# RobotCtrl_Base_Power.net
KiCad netlist of a schematic drawn in Altium Designer
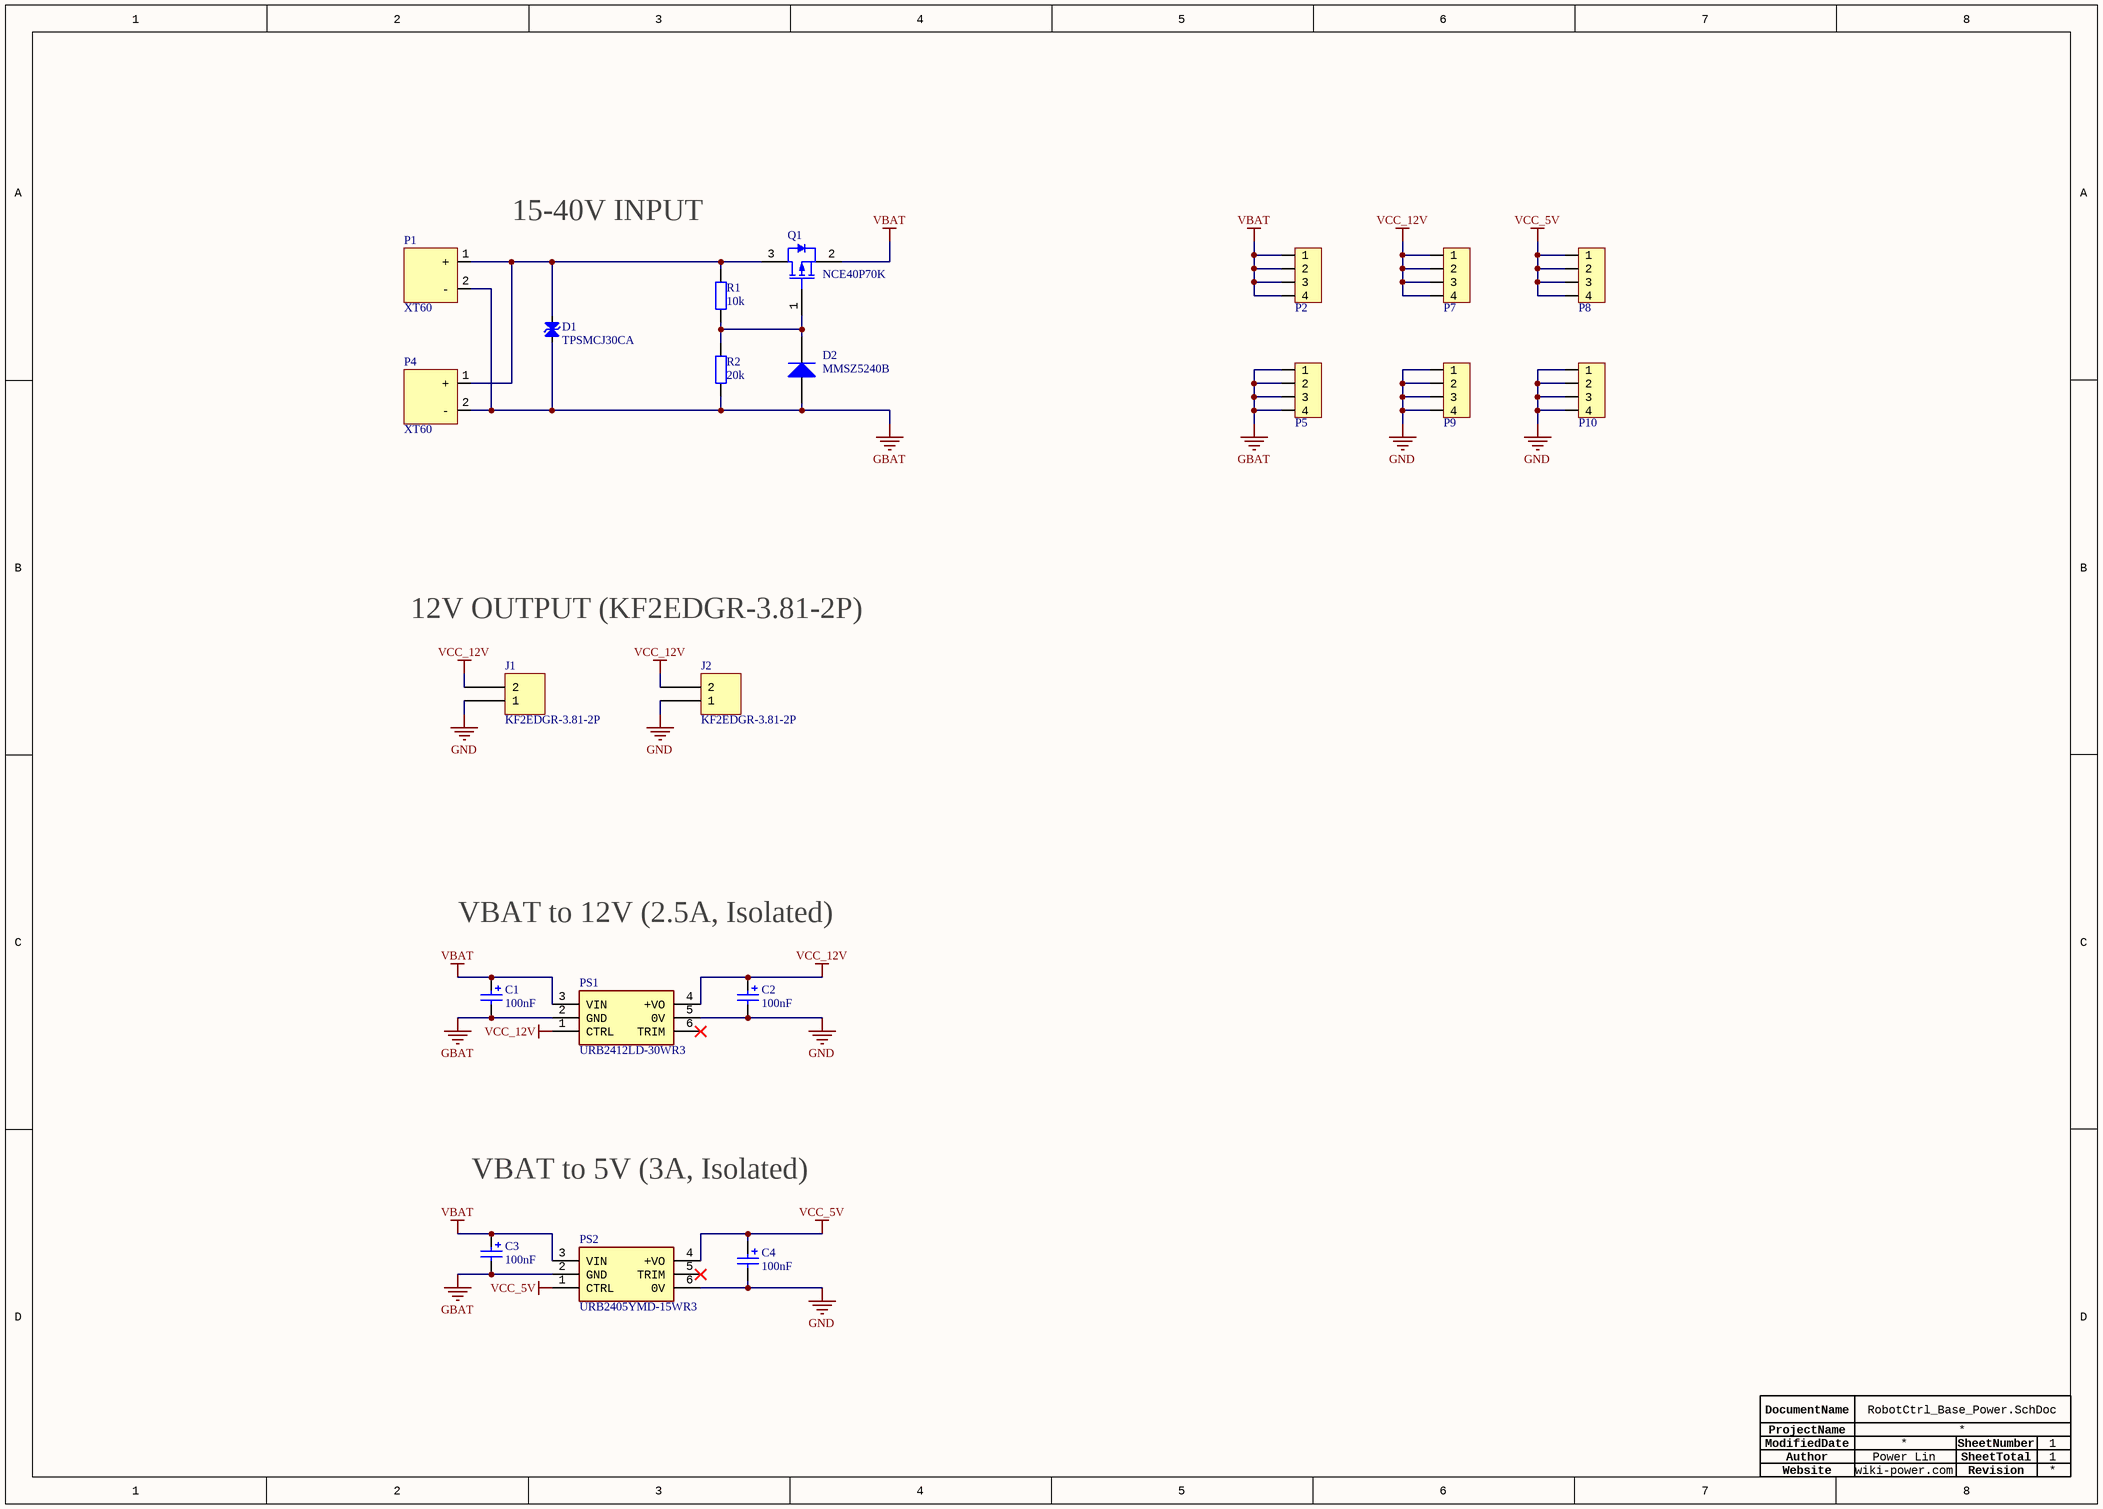
[diagram p0: RobotCtrl_Base_Power.SchDoc]

(export (version "E")
  (design (tool "Eeschema 10.0.6"))
  (components
    (comp (ref "C1")
      (value "100nF")
      (footprint "CAP-AUX-3216")
      (description "KM101M050F115A")
      (libsource (lib "Power_Lib_Altium") (part "CAP-POL"))
    )
    (comp (ref "C2")
      (value "100nF")
      (footprint "CAP-AUX-3216")
      (description "KM101M050F115A")
      (libsource (lib "Power_Lib_Altium") (part "CAP-POL"))
    )
    (comp (ref "C3")
      (value "100nF")
      (footprint "CAP-AUX-3216")
      (description "KM101M050F115A")
      (libsource (lib "Power_Lib_Altium") (part "CAP-POL"))
    )
    (comp (ref "C4")
      (value "100nF")
      (footprint "CAP-AUX-3216")
      (description "KM101M050F115A")
      (libsource (lib "Power_Lib_Altium") (part "CAP-POL"))
    )
    (comp (ref "D1")
      (value "TPSMCJ30CA")
      (footprint "DO-214AB/SMC")
      (libsource (lib "Power_Lib_Altium") (part "TVS_C"))
    )
    (comp (ref "D2")
      (value "MMSZ5240B")
      (footprint "SOD_123")
      (description "稳压 10V")
      (libsource (lib "Power_Lib_Altium") (part "DIODE"))
    )
    (comp (ref "J1")
      (value "KF2EDGR-3.81-2P")
      (footprint "FCI 06-381-2PIN")
      (description "TERM BLOCK HDR 2POS 90DEG 3.81MM")
      (fields (field (name "PART NUMBER") "OQ0232510000G") (field (name "MANUFACTURER") "Amphenol Anytek"))
      (libsource (lib "Power_Lib_Altium") (part "KF2EDGR-3.81-2P"))
    )
    (comp (ref "J2")
      (value "KF2EDGR-3.81-2P")
      (footprint "FCI 06-381-2PIN")
      (description "TERM BLOCK HDR 2POS 90DEG 3.81MM")
      (fields (field (name "PART NUMBER") "OQ0232510000G") (field (name "MANUFACTURER") "Amphenol Anytek"))
      (libsource (lib "Power_Lib_Altium") (part "KF2EDGR-3.81-2P"))
    )
    (comp (ref "P1")
      (value "XT60")
      (footprint "XT60PW-M")
      (libsource (lib "Power_Lib_Altium") (part "XT30/60"))
    )
    (comp (ref "P2")
      (value "HDR1x4_2.54")
      (footprint "HDR1x4_2.54_180")
      (description "Header")
      (libsource (lib "Power_Lib_Altium") (part "HDR1x4_2.54"))
    )
    (comp (ref "P4")
      (value "XT60")
      (footprint "XT60PW-M")
      (libsource (lib "Power_Lib_Altium") (part "XT30/60"))
    )
    (comp (ref "P5")
      (value "HDR1x4_2.54")
      (footprint "HDR1x4_2.54_180")
      (description "Header")
      (libsource (lib "Power_Lib_Altium") (part "HDR1x4_2.54"))
    )
    (comp (ref "P7")
      (value "HDR1x4_2.54")
      (footprint "HDR1x4_2.54_180")
      (description "Header")
      (libsource (lib "Power_Lib_Altium") (part "HDR1x4_2.54"))
    )
    (comp (ref "P8")
      (value "HDR1x4_2.54")
      (footprint "HDR1x4_2.54_180")
      (description "Header")
      (libsource (lib "Power_Lib_Altium") (part "HDR1x4_2.54"))
    )
    (comp (ref "P9")
      (value "HDR1x4_2.54")
      (footprint "HDR1x4_2.54_180")
      (description "Header")
      (libsource (lib "Power_Lib_Altium") (part "HDR1x4_2.54"))
    )
    (comp (ref "P10")
      (value "HDR1x4_2.54")
      (footprint "HDR1x4_2.54_180")
      (description "Header")
      (libsource (lib "Power_Lib_Altium") (part "HDR1x4_2.54"))
    )
    (comp (ref "PS1")
      (value "URB2412LD-30WR3")
      (footprint "URB2412LD30WR3")
      (description "金升阳隔离电源")
      (fields (field (name "MANUFACTURER_PART_NUMBER") "URB2412LD-30WHR3"))
      (libsource (lib "Power_Lib_Altium") (part "URB2412LD-30WR3"))
    )
    (comp (ref "PS2")
      (value "URB2405YMD-15WR3")
      (footprint "URB2405YMD15WR3")
      (description "金升阳隔离电源")
      (fields (field (name "MANUFACTURER_PART_NUMBER") "URB2405YMD-10WR3"))
      (libsource (lib "Power_Lib_Altium") (part "URB2405YMD-15WR3"))
    )
    (comp (ref "Q1")
      (value "NCE40P70K")
      (footprint "TO-252")
      (fields (field (name "MANUFACTURER") "NCE Power"))
      (libsource (lib "Power_Lib_Altium") (part "P-MOS"))
    )
    (comp (ref "R1")
      (value "10k")
      (footprint "R-0603")
      (description "贴片电阻")
      (libsource (lib "Power_Lib_Altium") (part "RES"))
    )
    (comp (ref "R2")
      (value "20k")
      (footprint "R-0603")
      (description "贴片电阻")
      (libsource (lib "Power_Lib_Altium") (part "RES"))
    )
  )
  (nets
    (net (code "1") (name "GBAT") (class "Default")
      (node (ref "C1") (pin "2") (pinfunction "2_2") (pintype "passive"))
      (node (ref "C3") (pin "2") (pinfunction "2_2") (pintype "passive"))
      (node (ref "D1") (pin "1") (pinfunction "1_1") (pintype "passive"))
      (node (ref "D2") (pin "1") (pinfunction "A_1") (pintype "passive"))
      (node (ref "P1") (pin "2") (pinfunction "-_2") (pintype "passive"))
      (node (ref "P4") (pin "2") (pinfunction "-_2") (pintype "passive"))
      (node (ref "P5") (pin "1") (pinfunction "1_1") (pintype "passive"))
      (node (ref "P5") (pin "2") (pinfunction "2_2") (pintype "passive"))
      (node (ref "P5") (pin "3") (pinfunction "3_3") (pintype "passive"))
      (node (ref "P5") (pin "4") (pinfunction "4_4") (pintype "passive"))
      (node (ref "PS1") (pin "2") (pinfunction "GND_2") (pintype "passive"))
      (node (ref "PS2") (pin "2") (pinfunction "GND_2") (pintype "passive"))
      (node (ref "R2") (pin "2") (pinfunction "2_2") (pintype "passive"))
    )
    (net (code "2") (name "GND") (class "Default")
      (node (ref "C2") (pin "2") (pinfunction "2_2") (pintype "passive"))
      (node (ref "C4") (pin "2") (pinfunction "2_2") (pintype "passive"))
      (node (ref "J1") (pin "1") (pinfunction "1_1") (pintype "passive"))
      (node (ref "J2") (pin "1") (pinfunction "1_1") (pintype "passive"))
      (node (ref "P10") (pin "1") (pinfunction "1_1") (pintype "passive"))
      (node (ref "P10") (pin "2") (pinfunction "2_2") (pintype "passive"))
      (node (ref "P10") (pin "3") (pinfunction "3_3") (pintype "passive"))
      (node (ref "P10") (pin "4") (pinfunction "4_4") (pintype "passive"))
      (node (ref "P9") (pin "1") (pinfunction "1_1") (pintype "passive"))
      (node (ref "P9") (pin "2") (pinfunction "2_2") (pintype "passive"))
      (node (ref "P9") (pin "3") (pinfunction "3_3") (pintype "passive"))
      (node (ref "P9") (pin "4") (pinfunction "4_4") (pintype "passive"))
      (node (ref "PS1") (pin "5") (pinfunction "0V_5") (pintype "passive"))
      (node (ref "PS2") (pin "6") (pinfunction "0V_6") (pintype "passive"))
    )
    (net (code "3") (name "Net-(D2-K)") (class "Default")
      (node (ref "D2") (pin "2") (pinfunction "K_2") (pintype "passive"))
      (node (ref "Q1") (pin "1") (pinfunction "GATE_1") (pintype "passive"))
      (node (ref "R1") (pin "2") (pinfunction "2_2") (pintype "passive"))
      (node (ref "R2") (pin "1") (pinfunction "1_1") (pintype "passive"))
    )
    (net (code "4") (name "Net-(P1-+)") (class "Default")
      (node (ref "D1") (pin "2") (pinfunction "2_2") (pintype "passive"))
      (node (ref "P1") (pin "1") (pinfunction "+_1") (pintype "passive"))
      (node (ref "P4") (pin "1") (pinfunction "+_1") (pintype "passive"))
      (node (ref "Q1") (pin "3") (pinfunction "DRAIN_3") (pintype "passive"))
      (node (ref "R1") (pin "1") (pinfunction "1_1") (pintype "passive"))
    )
    (net (code "5") (name "VBAT") (class "Default")
      (node (ref "C1") (pin "1") (pinfunction "1_1") (pintype "passive"))
      (node (ref "C3") (pin "1") (pinfunction "1_1") (pintype "passive"))
      (node (ref "P2") (pin "1") (pinfunction "1_1") (pintype "passive"))
      (node (ref "P2") (pin "2") (pinfunction "2_2") (pintype "passive"))
      (node (ref "P2") (pin "3") (pinfunction "3_3") (pintype "passive"))
      (node (ref "P2") (pin "4") (pinfunction "4_4") (pintype "passive"))
      (node (ref "PS1") (pin "3") (pinfunction "VIN_3") (pintype "passive"))
      (node (ref "PS2") (pin "3") (pinfunction "VIN_3") (pintype "passive"))
      (node (ref "Q1") (pin "2") (pinfunction "SOURCE_2") (pintype "passive"))
    )
    (net (code "6") (name "VCC_5V") (class "Default")
      (node (ref "C4") (pin "1") (pinfunction "1_1") (pintype "passive"))
      (node (ref "P8") (pin "1") (pinfunction "1_1") (pintype "passive"))
      (node (ref "P8") (pin "2") (pinfunction "2_2") (pintype "passive"))
      (node (ref "P8") (pin "3") (pinfunction "3_3") (pintype "passive"))
      (node (ref "P8") (pin "4") (pinfunction "4_4") (pintype "passive"))
      (node (ref "PS2") (pin "1") (pinfunction "CTRL_1") (pintype "passive"))
      (node (ref "PS2") (pin "4") (pinfunction "+VO_4") (pintype "passive"))
    )
    (net (code "7") (name "VCC_12V") (class "Default")
      (node (ref "C2") (pin "1") (pinfunction "1_1") (pintype "passive"))
      (node (ref "J1") (pin "2") (pinfunction "2_2") (pintype "passive"))
      (node (ref "J2") (pin "2") (pinfunction "2_2") (pintype "passive"))
      (node (ref "P7") (pin "1") (pinfunction "1_1") (pintype "passive"))
      (node (ref "P7") (pin "2") (pinfunction "2_2") (pintype "passive"))
      (node (ref "P7") (pin "3") (pinfunction "3_3") (pintype "passive"))
      (node (ref "P7") (pin "4") (pinfunction "4_4") (pintype "passive"))
      (node (ref "PS1") (pin "1") (pinfunction "CTRL_1") (pintype "passive"))
      (node (ref "PS1") (pin "4") (pinfunction "+VO_4") (pintype "passive"))
    )
    (net (code "8") (name "unconnected-(PS1-TRIM-Pad6)") (class "Default")
      (node (ref "PS1") (pin "6") (pinfunction "TRIM_6") (pintype "passive+no_connect"))
    )
    (net (code "9") (name "unconnected-(PS2-TRIM-Pad5)") (class "Default")
      (node (ref "PS2") (pin "5") (pinfunction "TRIM_5") (pintype "passive+no_connect"))
    )
  )
)
